# Controller.net
KiCad netlist of a schematic drawn in EAGLE
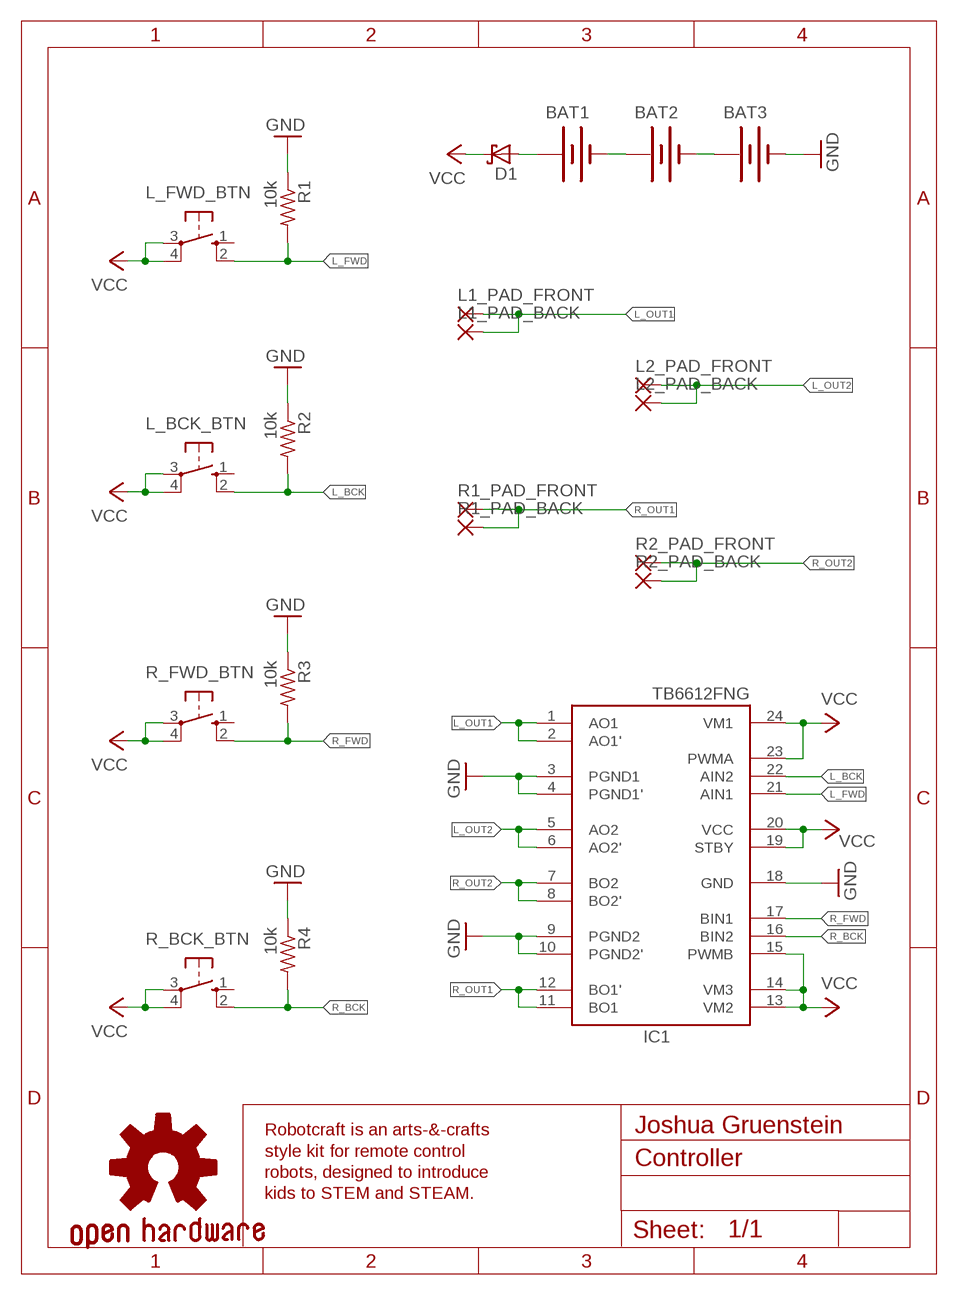
[diagram p0: schematic, sheet 1]

(export (version "E")
  (design (tool "Eeschema 10.0.6"))
  (components
    (comp (ref "BAT1")
      (value "BATTERYAA-KIT")
      (footprint "eagle-import:BATTERY-AA-KIT")
      (libsource (lib "eagle-import") (part "BATTERYAA-KIT"))
    )
    (comp (ref "BAT2")
      (value "BATTERYAA-KIT")
      (footprint "eagle-import:BATTERY-AA-KIT")
      (libsource (lib "eagle-import") (part "BATTERYAA-KIT"))
    )
    (comp (ref "BAT3")
      (value "BATTERYAA-KIT")
      (footprint "eagle-import:BATTERY-AA-KIT")
      (libsource (lib "eagle-import") (part "BATTERYAA-KIT"))
    )
    (comp (ref "D1")
      (value "SCHOTTKY-DIODESMC")
      (footprint "eagle-import:SMC")
      (libsource (lib "eagle-import") (part "SCHOTTKY-DIODESMC"))
    )
    (comp (ref "GOLD_ORB_SM1")
      (value "OSHWLOGO_GOLD_ORB_MED")
      (footprint "eagle-import:OSHW1")
      (libsource (lib "eagle-import") (part "OSHWLOGO_GOLD_ORB_MED"))
    )
    (comp (ref "IC1")
      (value "TB6612FNG")
      (footprint "eagle-import:SSOP24")
      (libsource (lib "eagle-import") (part "TB6612FNG"))
    )
    (comp (ref "L1_PAD_BACK")
      (value "WIREPADSMD5-2,5")
      (footprint "eagle-import:5-2,5")
      (libsource (lib "eagle-import") (part "WIREPADSMD5-2,5"))
    )
    (comp (ref "L1_PAD_FRONT")
      (value "WIREPADSMD5-2,5")
      (footprint "eagle-import:5-2,5")
      (libsource (lib "eagle-import") (part "WIREPADSMD5-2,5"))
    )
    (comp (ref "L2_PAD_BACK")
      (value "WIREPADSMD5-2,5")
      (footprint "eagle-import:5-2,5")
      (libsource (lib "eagle-import") (part "WIREPADSMD5-2,5"))
    )
    (comp (ref "L2_PAD_FRONT")
      (value "WIREPADSMD5-2,5")
      (footprint "eagle-import:5-2,5")
      (libsource (lib "eagle-import") (part "WIREPADSMD5-2,5"))
    )
    (comp (ref "L_BCK_BTN")
      (value "40-XX")
      (footprint "eagle-import:B3F-40XX")
      (fields (field (name "MF") "OMRON COMPONENTS USA") (field (name "MPN") "B3F-4000"))
      (libsource (lib "eagle-import") (part "40-XX"))
    )
    (comp (ref "L_FWD_BTN")
      (value "40-XX")
      (footprint "eagle-import:B3F-40XX")
      (fields (field (name "MF") "OMRON COMPONENTS USA") (field (name "MPN") "B3F-4000"))
      (libsource (lib "eagle-import") (part "40-XX"))
    )
    (comp (ref "R1")
      (value "10k")
      (footprint "eagle-import:R0805")
      (libsource (lib "eagle-import") (part "R-US_R0805"))
    )
    (comp (ref "R1_PAD_BACK")
      (value "WIREPADSMD5-2,5")
      (footprint "eagle-import:5-2,5")
      (libsource (lib "eagle-import") (part "WIREPADSMD5-2,5"))
    )
    (comp (ref "R1_PAD_FRONT")
      (value "WIREPADSMD5-2,5")
      (footprint "eagle-import:5-2,5")
      (libsource (lib "eagle-import") (part "WIREPADSMD5-2,5"))
    )
    (comp (ref "R2")
      (value "10k")
      (footprint "eagle-import:R0805")
      (libsource (lib "eagle-import") (part "R-US_R0805"))
    )
    (comp (ref "R2_PAD_BACK")
      (value "WIREPADSMD5-2,5")
      (footprint "eagle-import:5-2,5")
      (libsource (lib "eagle-import") (part "WIREPADSMD5-2,5"))
    )
    (comp (ref "R2_PAD_FRONT")
      (value "WIREPADSMD5-2,5")
      (footprint "eagle-import:5-2,5")
      (libsource (lib "eagle-import") (part "WIREPADSMD5-2,5"))
    )
    (comp (ref "R3")
      (value "10k")
      (footprint "eagle-import:R0805")
      (libsource (lib "eagle-import") (part "R-US_R0805"))
    )
    (comp (ref "R4")
      (value "10k")
      (footprint "eagle-import:R0805")
      (libsource (lib "eagle-import") (part "R-US_R0805"))
    )
    (comp (ref "R_BCK_BTN")
      (value "40-XX")
      (footprint "eagle-import:B3F-40XX")
      (fields (field (name "MF") "OMRON COMPONENTS USA") (field (name "MPN") "B3F-4000"))
      (libsource (lib "eagle-import") (part "40-XX"))
    )
    (comp (ref "R_FWD_BTN")
      (value "40-XX")
      (footprint "eagle-import:B3F-40XX")
      (fields (field (name "MF") "OMRON COMPONENTS USA") (field (name "MPN") "B3F-4000"))
      (libsource (lib "eagle-import") (part "40-XX"))
    )
  )
  (nets
    (net (code "1") (name "GND") (class "Default")
      (node (ref "BAT3") (pin "GND@1") (pinfunction "-_GND@1") (pintype "power_in"))
      (node (ref "IC1") (pin "10") (pinfunction "PGND2'_10") (pintype "power_in"))
      (node (ref "IC1") (pin "18") (pinfunction "GND_18") (pintype "power_in"))
      (node (ref "IC1") (pin "3") (pinfunction "PGND1_3") (pintype "power_in"))
      (node (ref "IC1") (pin "4") (pinfunction "PGND1'_4") (pintype "power_in"))
      (node (ref "IC1") (pin "9") (pinfunction "PGND2_9") (pintype "power_in"))
      (node (ref "R1") (pin "1") (pinfunction "1_1") (pintype "passive"))
      (node (ref "R2") (pin "1") (pinfunction "1_1") (pintype "passive"))
      (node (ref "R3") (pin "1") (pinfunction "1_1") (pintype "passive"))
      (node (ref "R4") (pin "1") (pinfunction "1_1") (pintype "passive"))
    )
    (net (code "2") (name "L_BCK") (class "Default")
      (node (ref "IC1") (pin "22") (pinfunction "AIN2_22") (pintype "input"))
      (node (ref "L_BCK_BTN") (pin "2") (pinfunction "S1_2") (pintype "passive"))
      (node (ref "R2") (pin "2") (pinfunction "2_2") (pintype "passive"))
    )
    (net (code "3") (name "L_FWD") (class "Default")
      (node (ref "IC1") (pin "21") (pinfunction "AIN1_21") (pintype "input"))
      (node (ref "L_FWD_BTN") (pin "2") (pinfunction "S1_2") (pintype "passive"))
      (node (ref "R1") (pin "2") (pinfunction "2_2") (pintype "passive"))
    )
    (net (code "4") (name "L_OUT1") (class "Default")
      (node (ref "IC1") (pin "1") (pinfunction "AO1_1") (pintype "output"))
      (node (ref "IC1") (pin "2") (pinfunction "AO1'_2") (pintype "output"))
      (node (ref "L1_PAD_BACK") (pin "1") (pinfunction "P_1") (pintype "passive"))
      (node (ref "L1_PAD_FRONT") (pin "1") (pinfunction "P_1") (pintype "passive"))
    )
    (net (code "5") (name "L_OUT2") (class "Default")
      (node (ref "IC1") (pin "5") (pinfunction "AO2_5") (pintype "output"))
      (node (ref "IC1") (pin "6") (pinfunction "AO2'_6") (pintype "output"))
      (node (ref "L2_PAD_BACK") (pin "1") (pinfunction "P_1") (pintype "passive"))
      (node (ref "L2_PAD_FRONT") (pin "1") (pinfunction "P_1") (pintype "passive"))
    )
    (net (code "6") (name "Net-(BAT1-+)") (class "Default")
      (node (ref "BAT1") (pin "PWR@1") (pinfunction "+_PWR@1") (pintype "power_in"))
      (node (ref "D1") (pin "A") (pinfunction "A_A") (pintype "passive"))
    )
    (net (code "7") (name "Net-(BAT1--)") (class "Default")
      (node (ref "BAT1") (pin "GND@1") (pinfunction "-_GND@1") (pintype "power_in"))
      (node (ref "BAT2") (pin "PWR@1") (pinfunction "+_PWR@1") (pintype "power_in"))
    )
    (net (code "8") (name "Net-(BAT2--)") (class "Default")
      (node (ref "BAT2") (pin "GND@1") (pinfunction "-_GND@1") (pintype "power_in"))
      (node (ref "BAT3") (pin "PWR@1") (pinfunction "+_PWR@1") (pintype "power_in"))
    )
    (net (code "9") (name "R_BCK") (class "Default")
      (node (ref "IC1") (pin "16") (pinfunction "BIN2_16") (pintype "input"))
      (node (ref "R4") (pin "2") (pinfunction "2_2") (pintype "passive"))
      (node (ref "R_BCK_BTN") (pin "2") (pinfunction "S1_2") (pintype "passive"))
    )
    (net (code "10") (name "R_FWD") (class "Default")
      (node (ref "IC1") (pin "17") (pinfunction "BIN1_17") (pintype "input"))
      (node (ref "R3") (pin "2") (pinfunction "2_2") (pintype "passive"))
      (node (ref "R_FWD_BTN") (pin "2") (pinfunction "S1_2") (pintype "passive"))
    )
    (net (code "11") (name "R_OUT1") (class "Default")
      (node (ref "IC1") (pin "11") (pinfunction "BO1_11") (pintype "output"))
      (node (ref "IC1") (pin "12") (pinfunction "BO1'_12") (pintype "output"))
      (node (ref "R1_PAD_BACK") (pin "1") (pinfunction "P_1") (pintype "passive"))
      (node (ref "R1_PAD_FRONT") (pin "1") (pinfunction "P_1") (pintype "passive"))
    )
    (net (code "12") (name "R_OUT2") (class "Default")
      (node (ref "IC1") (pin "7") (pinfunction "BO2_7") (pintype "output"))
      (node (ref "IC1") (pin "8") (pinfunction "BO2'_8") (pintype "output"))
      (node (ref "R2_PAD_BACK") (pin "1") (pinfunction "P_1") (pintype "passive"))
      (node (ref "R2_PAD_FRONT") (pin "1") (pinfunction "P_1") (pintype "passive"))
    )
    (net (code "13") (name "VCC") (class "Default")
      (node (ref "D1") (pin "C") (pinfunction "C_C") (pintype "passive"))
      (node (ref "IC1") (pin "13") (pinfunction "VM2_13") (pintype "power_in"))
      (node (ref "IC1") (pin "14") (pinfunction "VM3_14") (pintype "power_in"))
      (node (ref "IC1") (pin "15") (pinfunction "PWMB_15") (pintype "input"))
      (node (ref "IC1") (pin "19") (pinfunction "STBY_19") (pintype "input"))
      (node (ref "IC1") (pin "20") (pinfunction "VCC_20") (pintype "power_in"))
      (node (ref "IC1") (pin "23") (pinfunction "PWMA_23") (pintype "input"))
      (node (ref "IC1") (pin "24") (pinfunction "VM1_24") (pintype "power_in"))
      (node (ref "L_BCK_BTN") (pin "3") (pinfunction "P_3") (pintype "passive"))
      (node (ref "L_BCK_BTN") (pin "4") (pinfunction "P1_4") (pintype "passive"))
      (node (ref "L_FWD_BTN") (pin "3") (pinfunction "P_3") (pintype "passive"))
      (node (ref "L_FWD_BTN") (pin "4") (pinfunction "P1_4") (pintype "passive"))
      (node (ref "R_BCK_BTN") (pin "3") (pinfunction "P_3") (pintype "passive"))
      (node (ref "R_BCK_BTN") (pin "4") (pinfunction "P1_4") (pintype "passive"))
      (node (ref "R_FWD_BTN") (pin "3") (pinfunction "P_3") (pintype "passive"))
      (node (ref "R_FWD_BTN") (pin "4") (pinfunction "P1_4") (pintype "passive"))
    )
    (net (code "14") (name "unconnected-(L_BCK_BTN-S-Pad1)") (class "Default")
      (node (ref "L_BCK_BTN") (pin "1") (pinfunction "S_1") (pintype "passive"))
    )
    (net (code "15") (name "unconnected-(L_FWD_BTN-S-Pad1)") (class "Default")
      (node (ref "L_FWD_BTN") (pin "1") (pinfunction "S_1") (pintype "passive"))
    )
    (net (code "16") (name "unconnected-(R_BCK_BTN-S-Pad1)") (class "Default")
      (node (ref "R_BCK_BTN") (pin "1") (pinfunction "S_1") (pintype "passive"))
    )
    (net (code "17") (name "unconnected-(R_FWD_BTN-S-Pad1)") (class "Default")
      (node (ref "R_FWD_BTN") (pin "1") (pinfunction "S_1") (pintype "passive"))
    )
  )
)
